# Digital_IO.net
KiCad netlist of a schematic drawn in Altium Designer
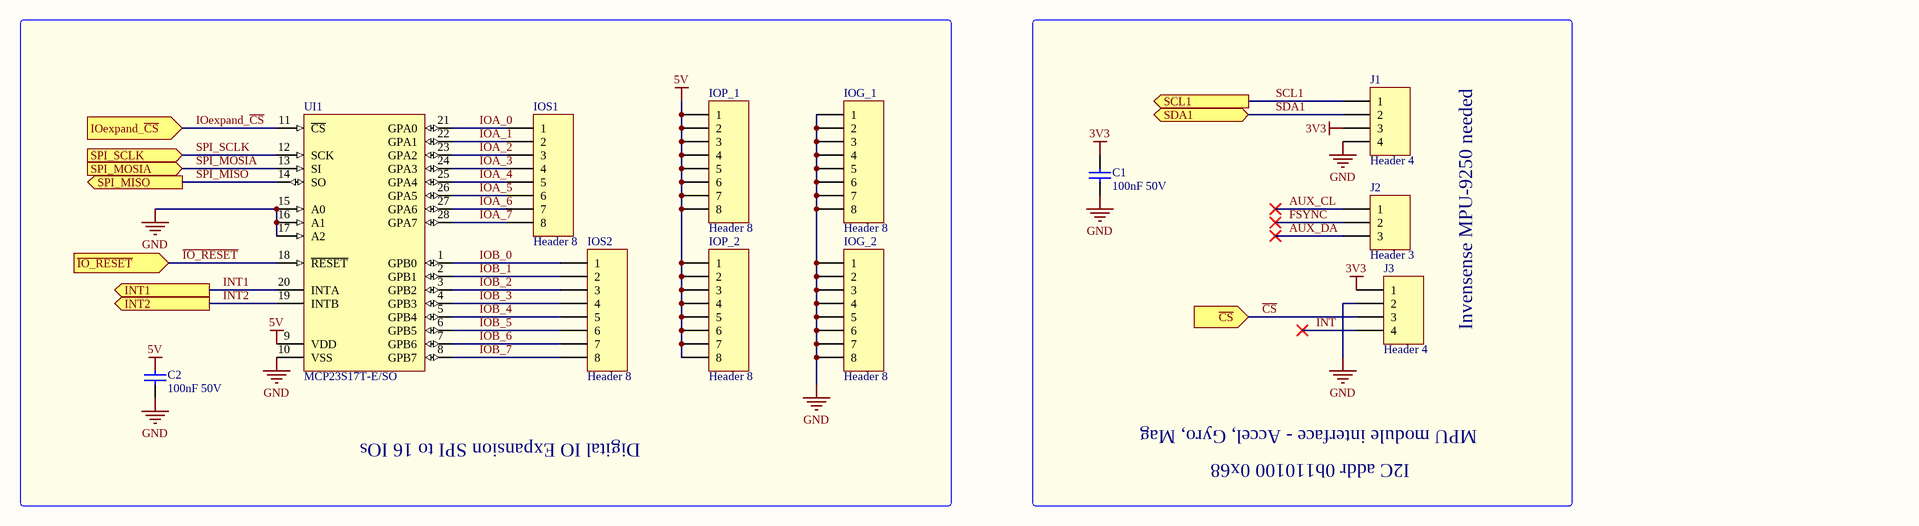
[diagram p0: Digital_IO.SchDoc]

(export (version "E")
  (design (tool "Eeschema 10.0.6"))
  (components
    (comp (ref "C1")
      (value "100nF 50V")
      (footprint "0603C_L")
      (fields
        (field (name "MANUFACTURER") "Yageo")
        (field (name "MANUFACTURER PART NUMBER") "CC0603ZRY5V9BB104")
        (field (name "TOLERANCE") "-20%, +80%")
      )
      (libsource (lib "WCT") (part "Cap101nF_50V_0603"))
    )
    (comp (ref "C2")
      (value "100nF 50V")
      (footprint "0603C_L")
      (fields
        (field (name "MANUFACTURER") "Yageo")
        (field (name "MANUFACTURER PART NUMBER") "CC0603ZRY5V9BB104")
        (field (name "TOLERANCE") "-20%, +80%")
      )
      (libsource (lib "WCT") (part "Cap101nF_50V_0603"))
    )
    (comp (ref "IOG_1")
      (value "Header 8")
      (footprint "HDR1X8")
      (description "Header, 8-Pin")
      (fields (field (name "PUBLISHER") "Altium Limited"))
      (libsource (lib "Miscellaneous Connectors") (part "Header 8"))
    )
    (comp (ref "IOG_2")
      (value "Header 8")
      (footprint "HDR1X8")
      (description "Header, 8-Pin")
      (fields (field (name "PUBLISHER") "Altium Limited"))
      (libsource (lib "Miscellaneous Connectors") (part "Header 8"))
    )
    (comp (ref "IOP_1")
      (value "Header 8")
      (footprint "HDR1X8")
      (description "Header, 8-Pin")
      (fields (field (name "PUBLISHER") "Altium Limited"))
      (libsource (lib "Miscellaneous Connectors") (part "Header 8"))
    )
    (comp (ref "IOP_2")
      (value "Header 8")
      (footprint "HDR1X8")
      (description "Header, 8-Pin")
      (fields (field (name "PUBLISHER") "Altium Limited"))
      (libsource (lib "Miscellaneous Connectors") (part "Header 8"))
    )
    (comp (ref "IOS1")
      (value "Header 8")
      (footprint "HDR1X8")
      (description "Header, 8-Pin")
      (fields (field (name "PUBLISHER") "Altium Limited"))
      (libsource (lib "Miscellaneous Connectors") (part "Header 8"))
    )
    (comp (ref "IOS2")
      (value "Header 8")
      (footprint "HDR1X8")
      (description "Header, 8-Pin")
      (fields (field (name "PUBLISHER") "Altium Limited"))
      (libsource (lib "Miscellaneous Connectors") (part "Header 8"))
    )
    (comp (ref "J1")
      (value "Header 4")
      (footprint "HDR1X4")
      (description "Header, 4-Pin")
      (fields (field (name "PUBLISHER") "Altium Limited"))
      (libsource (lib "Miscellaneous Connectors") (part "Header 4"))
    )
    (comp (ref "J2")
      (value "Header 3")
      (footprint "HDR1X3")
      (description "Header, 3-Pin")
      (fields (field (name "PUBLISHER") "Altium Limited"))
      (libsource (lib "Miscellaneous Connectors") (part "Header 3"))
    )
    (comp (ref "J3")
      (value "Header 4")
      (footprint "HDR1X4")
      (description "Header, 4-Pin")
      (fields (field (name "PUBLISHER") "Altium Limited"))
      (libsource (lib "Miscellaneous Connectors") (part "Header 4"))
    )
    (comp (ref "UI1")
      (value "MCP23S17T-E/SO")
      (footprint "SOIC-SO28_L")
      (description "16-Bit I/O Expander with Serial Interface, 28-Pin SOIC, Extended Temperature, Tape and Reel")
      (libsource (lib "Altium Content Vault") (part "CMP-0186-00131-2"))
    )
  )
  (nets
    (net (code "1") (name "/AUX_CL") (class "Default")
      (node (ref "J2") (pin "1") (pinfunction "1_1") (pintype "passive+no_connect"))
    )
    (net (code "2") (name "/AUX_DA") (class "Default")
      (node (ref "J2") (pin "3") (pinfunction "3_3") (pintype "passive+no_connect"))
    )
    (net (code "3") (name "/FSYNC") (class "Default")
      (node (ref "J2") (pin "2") (pinfunction "2_2") (pintype "passive+no_connect"))
    )
    (net (code "4") (name "/INT") (class "Default")
      (node (ref "J3") (pin "4") (pinfunction "4_4") (pintype "passive+no_connect"))
    )
    (net (code "5") (name "/INT1") (class "Default")
      (node (ref "UI1") (pin "20") (pinfunction "INTA_20") (pintype "open_collector"))
    )
    (net (code "6") (name "/INT2") (class "Default")
      (node (ref "UI1") (pin "19") (pinfunction "INTB_19") (pintype "open_collector"))
    )
    (net (code "7") (name "/IOA_0") (class "Default")
      (node (ref "IOS1") (pin "1") (pinfunction "1_1") (pintype "passive"))
      (node (ref "UI1") (pin "21") (pinfunction "GPA0_21") (pintype "bidirectional"))
    )
    (net (code "8") (name "/IOA_1") (class "Default")
      (node (ref "IOS1") (pin "2") (pinfunction "2_2") (pintype "passive"))
      (node (ref "UI1") (pin "22") (pinfunction "GPA1_22") (pintype "bidirectional"))
    )
    (net (code "9") (name "/IOA_2") (class "Default")
      (node (ref "IOS1") (pin "3") (pinfunction "3_3") (pintype "passive"))
      (node (ref "UI1") (pin "23") (pinfunction "GPA2_23") (pintype "bidirectional"))
    )
    (net (code "10") (name "/IOA_3") (class "Default")
      (node (ref "IOS1") (pin "4") (pinfunction "4_4") (pintype "passive"))
      (node (ref "UI1") (pin "24") (pinfunction "GPA3_24") (pintype "bidirectional"))
    )
    (net (code "11") (name "/IOA_4") (class "Default")
      (node (ref "IOS1") (pin "5") (pinfunction "5_5") (pintype "passive"))
      (node (ref "UI1") (pin "25") (pinfunction "GPA4_25") (pintype "bidirectional"))
    )
    (net (code "12") (name "/IOA_5") (class "Default")
      (node (ref "IOS1") (pin "6") (pinfunction "6_6") (pintype "passive"))
      (node (ref "UI1") (pin "26") (pinfunction "GPA5_26") (pintype "bidirectional"))
    )
    (net (code "13") (name "/IOA_6") (class "Default")
      (node (ref "IOS1") (pin "7") (pinfunction "7_7") (pintype "passive"))
      (node (ref "UI1") (pin "27") (pinfunction "GPA6_27") (pintype "bidirectional"))
    )
    (net (code "14") (name "/IOA_7") (class "Default")
      (node (ref "IOS1") (pin "8") (pinfunction "8_8") (pintype "passive"))
      (node (ref "UI1") (pin "28") (pinfunction "GPA7_28") (pintype "bidirectional"))
    )
    (net (code "15") (name "/IOB_0") (class "Default")
      (node (ref "IOS2") (pin "1") (pinfunction "1_1") (pintype "passive"))
      (node (ref "UI1") (pin "1") (pinfunction "GPB0_1") (pintype "bidirectional"))
    )
    (net (code "16") (name "/IOB_1") (class "Default")
      (node (ref "IOS2") (pin "2") (pinfunction "2_2") (pintype "passive"))
      (node (ref "UI1") (pin "2") (pinfunction "GPB1_2") (pintype "bidirectional"))
    )
    (net (code "17") (name "/IOB_2") (class "Default")
      (node (ref "IOS2") (pin "3") (pinfunction "3_3") (pintype "passive"))
      (node (ref "UI1") (pin "3") (pinfunction "GPB2_3") (pintype "bidirectional"))
    )
    (net (code "18") (name "/IOB_3") (class "Default")
      (node (ref "IOS2") (pin "4") (pinfunction "4_4") (pintype "passive"))
      (node (ref "UI1") (pin "4") (pinfunction "GPB3_4") (pintype "bidirectional"))
    )
    (net (code "19") (name "/IOB_4") (class "Default")
      (node (ref "IOS2") (pin "5") (pinfunction "5_5") (pintype "passive"))
      (node (ref "UI1") (pin "5") (pinfunction "GPB4_5") (pintype "bidirectional"))
    )
    (net (code "20") (name "/IOB_5") (class "Default")
      (node (ref "IOS2") (pin "6") (pinfunction "6_6") (pintype "passive"))
      (node (ref "UI1") (pin "6") (pinfunction "GPB5_6") (pintype "bidirectional"))
    )
    (net (code "21") (name "/IOB_6") (class "Default")
      (node (ref "IOS2") (pin "7") (pinfunction "7_7") (pintype "passive"))
      (node (ref "UI1") (pin "7") (pinfunction "GPB6_7") (pintype "bidirectional"))
    )
    (net (code "22") (name "/IOB_7") (class "Default")
      (node (ref "IOS2") (pin "8") (pinfunction "8_8") (pintype "passive"))
      (node (ref "UI1") (pin "8") (pinfunction "GPB7_8") (pintype "bidirectional"))
    )
    (net (code "23") (name "/IO_RESET") (class "Default")
      (node (ref "UI1") (pin "18") (pinfunction "~{RESET}_18") (pintype "input"))
    )
    (net (code "24") (name "/IOexpand_~{CS}") (class "Default")
      (node (ref "UI1") (pin "11") (pinfunction "~{CS}_11") (pintype "input"))
    )
    (net (code "25") (name "/SCL1") (class "Default")
      (node (ref "J1") (pin "1") (pinfunction "1_1") (pintype "passive"))
    )
    (net (code "26") (name "/SDA1") (class "Default")
      (node (ref "J1") (pin "2") (pinfunction "2_2") (pintype "passive"))
    )
    (net (code "27") (name "/SPI_MISO") (class "Default")
      (node (ref "UI1") (pin "14") (pinfunction "SO_14") (pintype "bidirectional"))
    )
    (net (code "28") (name "/SPI_MOSIA") (class "Default")
      (node (ref "UI1") (pin "13") (pinfunction "SI_13") (pintype "input"))
    )
    (net (code "29") (name "/SPI_SCLK") (class "Default")
      (node (ref "UI1") (pin "12") (pinfunction "SCK_12") (pintype "input"))
    )
    (net (code "30") (name "/~{CS}") (class "Default")
      (node (ref "J3") (pin "3") (pinfunction "3_3") (pintype "passive"))
    )
    (net (code "31") (name "3V3") (class "Default")
      (node (ref "C1") (pin "2") (pinfunction "2_2") (pintype "passive"))
      (node (ref "J1") (pin "3") (pinfunction "3_3") (pintype "passive"))
      (node (ref "J3") (pin "1") (pinfunction "1_1") (pintype "passive"))
    )
    (net (code "32") (name "5V") (class "Default")
      (node (ref "IOP_1") (pin "1") (pinfunction "1_1") (pintype "passive"))
      (node (ref "IOP_1") (pin "2") (pinfunction "2_2") (pintype "passive"))
      (node (ref "IOP_1") (pin "3") (pinfunction "3_3") (pintype "passive"))
      (node (ref "IOP_1") (pin "4") (pinfunction "4_4") (pintype "passive"))
      (node (ref "IOP_1") (pin "5") (pinfunction "5_5") (pintype "passive"))
      (node (ref "IOP_1") (pin "6") (pinfunction "6_6") (pintype "passive"))
      (node (ref "IOP_1") (pin "7") (pinfunction "7_7") (pintype "passive"))
      (node (ref "IOP_1") (pin "8") (pinfunction "8_8") (pintype "passive"))
      (node (ref "IOP_2") (pin "1") (pinfunction "1_1") (pintype "passive"))
      (node (ref "IOP_2") (pin "2") (pinfunction "2_2") (pintype "passive"))
      (node (ref "IOP_2") (pin "3") (pinfunction "3_3") (pintype "passive"))
      (node (ref "IOP_2") (pin "4") (pinfunction "4_4") (pintype "passive"))
      (node (ref "IOP_2") (pin "5") (pinfunction "5_5") (pintype "passive"))
      (node (ref "IOP_2") (pin "6") (pinfunction "6_6") (pintype "passive"))
      (node (ref "IOP_2") (pin "7") (pinfunction "7_7") (pintype "passive"))
      (node (ref "IOP_2") (pin "8") (pinfunction "8_8") (pintype "passive"))
      (node (ref "UI1") (pin "9") (pinfunction "VDD_9") (pintype "power_in"))
    )
    (net (code "33") (name "GND") (class "Default")
      (node (ref "C1") (pin "1") (pinfunction "1_1") (pintype "passive"))
      (node (ref "C2") (pin "1") (pinfunction "1_1") (pintype "passive"))
      (node (ref "IOG_1") (pin "1") (pinfunction "1_1") (pintype "passive"))
      (node (ref "IOG_1") (pin "2") (pinfunction "2_2") (pintype "passive"))
      (node (ref "IOG_1") (pin "3") (pinfunction "3_3") (pintype "passive"))
      (node (ref "IOG_1") (pin "4") (pinfunction "4_4") (pintype "passive"))
      (node (ref "IOG_1") (pin "5") (pinfunction "5_5") (pintype "passive"))
      (node (ref "IOG_1") (pin "6") (pinfunction "6_6") (pintype "passive"))
      (node (ref "IOG_1") (pin "7") (pinfunction "7_7") (pintype "passive"))
      (node (ref "IOG_1") (pin "8") (pinfunction "8_8") (pintype "passive"))
      (node (ref "IOG_2") (pin "1") (pinfunction "1_1") (pintype "passive"))
      (node (ref "IOG_2") (pin "2") (pinfunction "2_2") (pintype "passive"))
      (node (ref "IOG_2") (pin "3") (pinfunction "3_3") (pintype "passive"))
      (node (ref "IOG_2") (pin "4") (pinfunction "4_4") (pintype "passive"))
      (node (ref "IOG_2") (pin "5") (pinfunction "5_5") (pintype "passive"))
      (node (ref "IOG_2") (pin "6") (pinfunction "6_6") (pintype "passive"))
      (node (ref "IOG_2") (pin "7") (pinfunction "7_7") (pintype "passive"))
      (node (ref "IOG_2") (pin "8") (pinfunction "8_8") (pintype "passive"))
      (node (ref "J1") (pin "4") (pinfunction "4_4") (pintype "passive"))
      (node (ref "J3") (pin "2") (pinfunction "2_2") (pintype "passive"))
      (node (ref "UI1") (pin "10") (pinfunction "VSS_10") (pintype "power_in"))
      (node (ref "UI1") (pin "15") (pinfunction "A0_15") (pintype "input"))
      (node (ref "UI1") (pin "16") (pinfunction "A1_16") (pintype "input"))
      (node (ref "UI1") (pin "17") (pinfunction "A2_17") (pintype "input"))
    )
    (net (code "34") (name "unconnected-(C2-Pad2)") (class "Default")
      (node (ref "C2") (pin "2") (pinfunction "2_2") (pintype "passive"))
    )
  )
)
